# EVMS3_Monitor.net
KiCad netlist of a schematic drawn in EAGLE
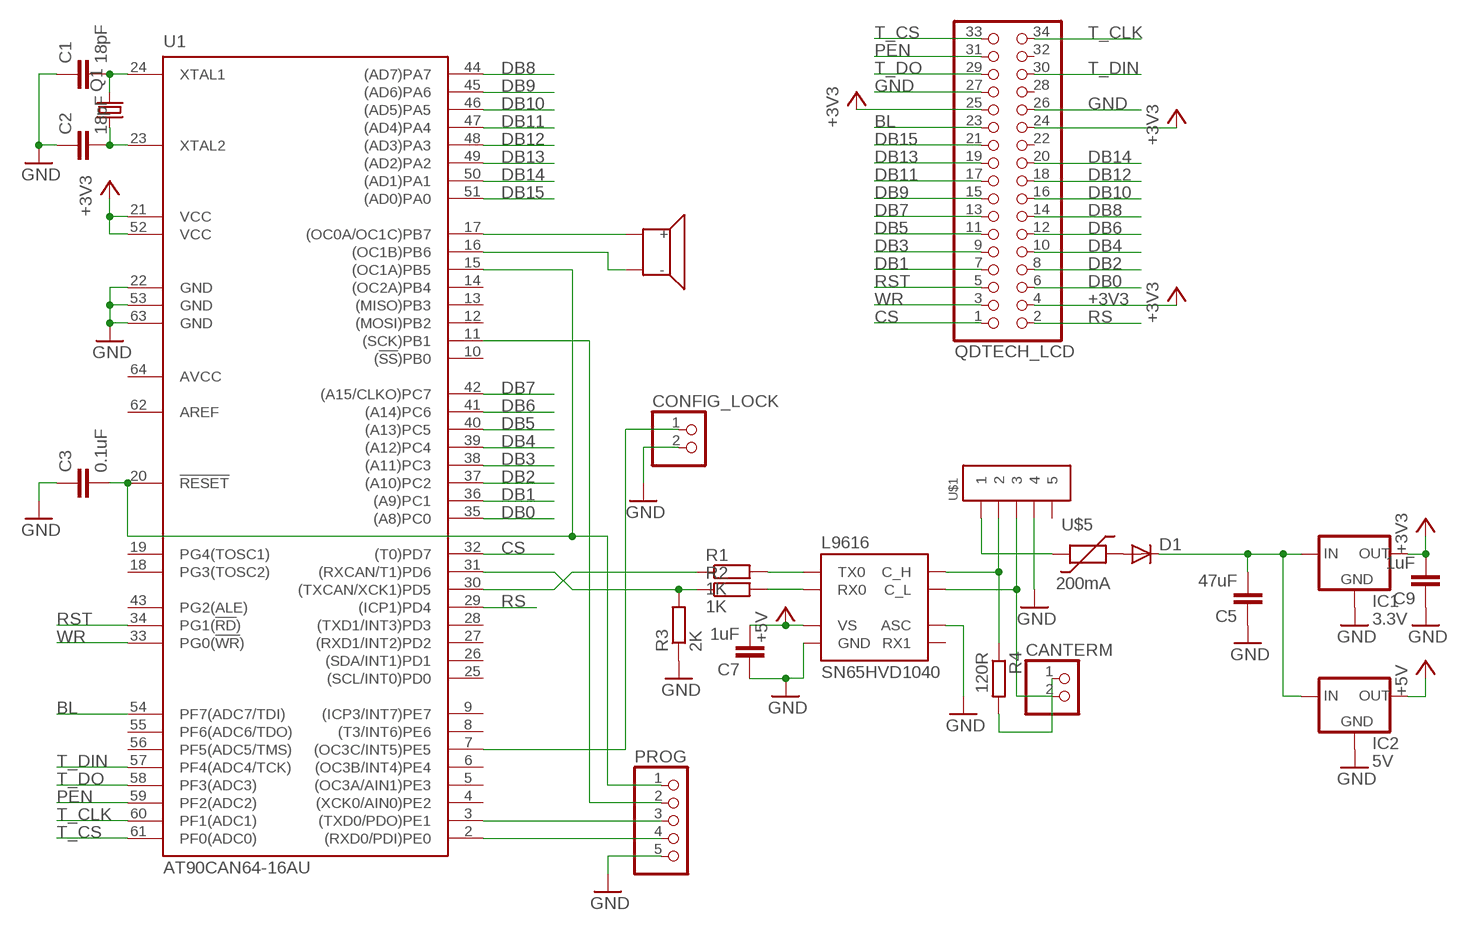
[diagram p0: schematic, sheet 1]

(export (version "E")
  (design (tool "Eeschema 10.0.6"))
  (components
    (comp (ref "C1")
      (value "18pF")
      (footprint "eagle-import:C0805")
      (libsource (lib "eagle-import") (part "C-EUC0805"))
    )
    (comp (ref "C2")
      (value "18pF")
      (footprint "eagle-import:C0805")
      (libsource (lib "eagle-import") (part "C-EUC0805"))
    )
    (comp (ref "C3")
      (value "0.1uF")
      (footprint "eagle-import:C1206")
      (libsource (lib "eagle-import") (part "C-EUC1206"))
    )
    (comp (ref "C5")
      (value "47uF")
      (footprint "eagle-import:C1206")
      (libsource (lib "eagle-import") (part "C-EUC1206"))
    )
    (comp (ref "C7")
      (value "1uF")
      (footprint "eagle-import:C1206")
      (libsource (lib "eagle-import") (part "C-EUC1206"))
    )
    (comp (ref "C9")
      (value "1uF")
      (footprint "eagle-import:C1206")
      (libsource (lib "eagle-import") (part "C-EUC1206"))
    )
    (comp (ref "CANTERM")
      (value "PINHD-1X2")
      (footprint "eagle-import:1X02")
      (libsource (lib "eagle-import") (part "PINHD-1X2"))
    )
    (comp (ref "CONFIG_LOCK")
      (value "PINHD-1X2")
      (footprint "eagle-import:1X02")
      (libsource (lib "eagle-import") (part "PINHD-1X2"))
    )
    (comp (ref "D1")
      (value "DIODE-SOD123")
      (footprint "eagle-import:SOD123")
      (libsource (lib "eagle-import") (part "DIODE-SOD123"))
    )
    (comp (ref "IC1")
      (value "3.3V")
      (footprint "eagle-import:SOT89R")
      (libsource (lib "eagle-import") (part "78LXXSOT89"))
    )
    (comp (ref "IC2")
      (value "5V")
      (footprint "eagle-import:SOT89R")
      (libsource (lib "eagle-import") (part "78LXXSOT89"))
    )
    (comp (ref "PROG")
      (value "PINHD-1X5")
      (footprint "eagle-import:1X05")
      (libsource (lib "eagle-import") (part "PINHD-1X5"))
    )
    (comp (ref "Q1")
      (value "CRYSTALCTS406")
      (footprint "eagle-import:CTS406")
      (libsource (lib "eagle-import") (part "CRYSTALCTS406"))
    )
    (comp (ref "QDTECH_LCD")
      (value "PINHD-2X17")
      (footprint "eagle-import:2X17")
      (libsource (lib "eagle-import") (part "PINHD-2X17"))
    )
    (comp (ref "R1")
      (value "1K")
      (footprint "eagle-import:R1206")
      (libsource (lib "eagle-import") (part "R-EU_R1206"))
    )
    (comp (ref "R2")
      (value "1K")
      (footprint "eagle-import:R1206")
      (libsource (lib "eagle-import") (part "R-EU_R1206"))
    )
    (comp (ref "R3")
      (value "2K")
      (footprint "eagle-import:R1206")
      (libsource (lib "eagle-import") (part "R-EU_R1206"))
    )
    (comp (ref "R4")
      (value "120R")
      (footprint "eagle-import:R1206")
      (libsource (lib "eagle-import") (part "R-EU_R1206"))
    )
    (comp (ref "SN65HVD1040")
      (value "L9616")
      (footprint "eagle-import:SOIC8")
      (libsource (lib "eagle-import") (part "L9616"))
    )
    (comp (ref "U$1")
      (value "MOLEX-39502-1005VERT")
      (footprint "eagle-import:MOLEX-39501-1005")
      (libsource (lib "eagle-import") (part "MOLEX-39502-1005VERT"))
    )
    (comp (ref "U$5")
      (value "200mA")
      (footprint "eagle-import:1206")
      (libsource (lib "eagle-import") (part "1206_POLYSWITCH"))
    )
    (comp (ref "U$6")
      (value "MURATA_PIEZO")
      (footprint "eagle-import:PKLCS1212E_PIEZO")
      (libsource (lib "eagle-import") (part "MURATA_PIEZO"))
    )
    (comp (ref "U1")
      (value "AT90CAN64-16AU")
      (footprint "eagle-import:TQFP64-0.8MM")
      (libsource (lib "eagle-import") (part "AT90CAN64-16AU"))
    )
  )
  (nets
    (net (code "1") (name "+3V3") (class "Default")
      (node (ref "C9") (pin "2") (pinfunction "2_2") (pintype "passive"))
      (node (ref "IC1") (pin "2") (pinfunction "OUT_2") (pintype "passive"))
      (node (ref "QDTECH_LCD") (pin "24") (pinfunction "24_24") (pintype "passive"))
      (node (ref "QDTECH_LCD") (pin "25") (pinfunction "25_25") (pintype "passive"))
      (node (ref "QDTECH_LCD") (pin "4") (pinfunction "4_4") (pintype "passive"))
      (node (ref "U1") (pin "21") (pinfunction "VCC_21") (pintype "power_in"))
      (node (ref "U1") (pin "52") (pinfunction "VCC_52") (pintype "power_in"))
    )
    (net (code "2") (name "+5V") (class "Default")
      (node (ref "C7") (pin "2") (pinfunction "2_2") (pintype "passive"))
      (node (ref "IC2") (pin "2") (pinfunction "OUT_2") (pintype "passive"))
      (node (ref "SN65HVD1040") (pin "P$3") (pinfunction "VS_P$3") (pintype "bidirectional"))
    )
    (net (code "3") (name "/AVCC") (class "Default")
      (node (ref "U1") (pin "64") (pinfunction "AVCC_64") (pintype "power_in"))
    )
    (net (code "4") (name "/BL") (class "Default")
      (node (ref "QDTECH_LCD") (pin "23") (pinfunction "23_23") (pintype "passive"))
      (node (ref "U1") (pin "54") (pinfunction "PF7(ADC7/TDI)_54") (pintype "bidirectional"))
    )
    (net (code "5") (name "/CS") (class "Default")
      (node (ref "QDTECH_LCD") (pin "1") (pinfunction "1_1") (pintype "passive"))
      (node (ref "U1") (pin "32") (pinfunction "(T0)PD7_32") (pintype "bidirectional"))
    )
    (net (code "6") (name "/DB0") (class "Default")
      (node (ref "QDTECH_LCD") (pin "6") (pinfunction "6_6") (pintype "passive"))
      (node (ref "U1") (pin "35") (pinfunction "(A8)PC0_35") (pintype "bidirectional"))
    )
    (net (code "7") (name "/DB1") (class "Default")
      (node (ref "QDTECH_LCD") (pin "7") (pinfunction "7_7") (pintype "passive"))
      (node (ref "U1") (pin "36") (pinfunction "(A9)PC1_36") (pintype "bidirectional"))
    )
    (net (code "8") (name "/DB2") (class "Default")
      (node (ref "QDTECH_LCD") (pin "8") (pinfunction "8_8") (pintype "passive"))
      (node (ref "U1") (pin "37") (pinfunction "(A10)PC2_37") (pintype "bidirectional"))
    )
    (net (code "9") (name "/DB3") (class "Default")
      (node (ref "QDTECH_LCD") (pin "9") (pinfunction "9_9") (pintype "passive"))
      (node (ref "U1") (pin "38") (pinfunction "(A11)PC3_38") (pintype "bidirectional"))
    )
    (net (code "10") (name "/DB4") (class "Default")
      (node (ref "QDTECH_LCD") (pin "10") (pinfunction "10_10") (pintype "passive"))
      (node (ref "U1") (pin "39") (pinfunction "(A12)PC4_39") (pintype "bidirectional"))
    )
    (net (code "11") (name "/DB5") (class "Default")
      (node (ref "QDTECH_LCD") (pin "11") (pinfunction "11_11") (pintype "passive"))
      (node (ref "U1") (pin "40") (pinfunction "(A13)PC5_40") (pintype "bidirectional"))
    )
    (net (code "12") (name "/DB6") (class "Default")
      (node (ref "QDTECH_LCD") (pin "12") (pinfunction "12_12") (pintype "passive"))
      (node (ref "U1") (pin "41") (pinfunction "(A14)PC6_41") (pintype "bidirectional"))
    )
    (net (code "13") (name "/DB7") (class "Default")
      (node (ref "QDTECH_LCD") (pin "13") (pinfunction "13_13") (pintype "passive"))
      (node (ref "U1") (pin "42") (pinfunction "(A15/CLKO)PC7_42") (pintype "bidirectional"))
    )
    (net (code "14") (name "/DB8") (class "Default")
      (node (ref "QDTECH_LCD") (pin "14") (pinfunction "14_14") (pintype "passive"))
      (node (ref "U1") (pin "44") (pinfunction "(AD7)PA7_44") (pintype "bidirectional"))
    )
    (net (code "15") (name "/DB9") (class "Default")
      (node (ref "QDTECH_LCD") (pin "15") (pinfunction "15_15") (pintype "passive"))
      (node (ref "U1") (pin "45") (pinfunction "(AD6)PA6_45") (pintype "bidirectional"))
    )
    (net (code "16") (name "/DB10") (class "Default")
      (node (ref "QDTECH_LCD") (pin "16") (pinfunction "16_16") (pintype "passive"))
      (node (ref "U1") (pin "46") (pinfunction "(AD5)PA5_46") (pintype "bidirectional"))
    )
    (net (code "17") (name "/DB11") (class "Default")
      (node (ref "QDTECH_LCD") (pin "17") (pinfunction "17_17") (pintype "passive"))
      (node (ref "U1") (pin "47") (pinfunction "(AD4)PA4_47") (pintype "bidirectional"))
    )
    (net (code "18") (name "/DB12") (class "Default")
      (node (ref "QDTECH_LCD") (pin "18") (pinfunction "18_18") (pintype "passive"))
      (node (ref "U1") (pin "48") (pinfunction "(AD3)PA3_48") (pintype "bidirectional"))
    )
    (net (code "19") (name "/DB13") (class "Default")
      (node (ref "QDTECH_LCD") (pin "19") (pinfunction "19_19") (pintype "passive"))
      (node (ref "U1") (pin "49") (pinfunction "(AD2)PA2_49") (pintype "bidirectional"))
    )
    (net (code "20") (name "/DB14") (class "Default")
      (node (ref "QDTECH_LCD") (pin "20") (pinfunction "20_20") (pintype "passive"))
      (node (ref "U1") (pin "50") (pinfunction "(AD1)PA1_50") (pintype "bidirectional"))
    )
    (net (code "21") (name "/DB15") (class "Default")
      (node (ref "QDTECH_LCD") (pin "21") (pinfunction "21_21") (pintype "passive"))
      (node (ref "U1") (pin "51") (pinfunction "(AD0)PA0_51") (pintype "bidirectional"))
    )
    (net (code "22") (name "/PEN") (class "Default")
      (node (ref "QDTECH_LCD") (pin "31") (pinfunction "31_31") (pintype "passive"))
      (node (ref "U1") (pin "59") (pinfunction "PF2(ADC2)_59") (pintype "bidirectional"))
    )
    (net (code "23") (name "/RS") (class "Default")
      (node (ref "QDTECH_LCD") (pin "2") (pinfunction "2_2") (pintype "passive"))
      (node (ref "U1") (pin "29") (pinfunction "(ICP1)PD4_29") (pintype "bidirectional"))
    )
    (net (code "24") (name "/RST") (class "Default")
      (node (ref "QDTECH_LCD") (pin "5") (pinfunction "5_5") (pintype "passive"))
      (node (ref "U1") (pin "34") (pinfunction "PG1(~{RD})_34") (pintype "bidirectional"))
    )
    (net (code "25") (name "/T_CLK") (class "Default")
      (node (ref "QDTECH_LCD") (pin "34") (pinfunction "34_34") (pintype "passive"))
      (node (ref "U1") (pin "60") (pinfunction "PF1(ADC1)_60") (pintype "bidirectional"))
    )
    (net (code "26") (name "/T_CS") (class "Default")
      (node (ref "QDTECH_LCD") (pin "33") (pinfunction "33_33") (pintype "passive"))
      (node (ref "U1") (pin "61") (pinfunction "PF0(ADC0)_61") (pintype "bidirectional"))
    )
    (net (code "27") (name "/T_DIN") (class "Default")
      (node (ref "QDTECH_LCD") (pin "30") (pinfunction "30_30") (pintype "passive"))
      (node (ref "U1") (pin "57") (pinfunction "PF4(ADC4/TCK)_57") (pintype "bidirectional"))
    )
    (net (code "28") (name "/T_DO") (class "Default")
      (node (ref "QDTECH_LCD") (pin "29") (pinfunction "29_29") (pintype "passive"))
      (node (ref "U1") (pin "58") (pinfunction "PF3(ADC3)_58") (pintype "bidirectional"))
    )
    (net (code "29") (name "/WR") (class "Default")
      (node (ref "QDTECH_LCD") (pin "3") (pinfunction "3_3") (pintype "passive"))
      (node (ref "U1") (pin "33") (pinfunction "PG0(~{WR})_33") (pintype "bidirectional"))
    )
    (net (code "30") (name "GND") (class "Default")
      (node (ref "C1") (pin "1") (pinfunction "1_1") (pintype "passive"))
      (node (ref "C2") (pin "1") (pinfunction "1_1") (pintype "passive"))
      (node (ref "C3") (pin "1") (pinfunction "1_1") (pintype "passive"))
      (node (ref "C5") (pin "1") (pinfunction "1_1") (pintype "passive"))
      (node (ref "C7") (pin "1") (pinfunction "1_1") (pintype "passive"))
      (node (ref "C9") (pin "1") (pinfunction "1_1") (pintype "passive"))
      (node (ref "CONFIG_LOCK") (pin "2") (pinfunction "2_2") (pintype "passive"))
      (node (ref "IC1") (pin "4") (pinfunction "GND_4") (pintype "input"))
      (node (ref "IC2") (pin "4") (pinfunction "GND_4") (pintype "input"))
      (node (ref "PROG") (pin "5") (pinfunction "5_5") (pintype "passive"))
      (node (ref "QDTECH_LCD") (pin "26") (pinfunction "26_26") (pintype "passive"))
      (node (ref "QDTECH_LCD") (pin "27") (pinfunction "27_27") (pintype "passive"))
      (node (ref "R3") (pin "1") (pinfunction "1_1") (pintype "passive"))
      (node (ref "SN65HVD1040") (pin "P$2") (pinfunction "GND_P$2") (pintype "bidirectional"))
      (node (ref "SN65HVD1040") (pin "P$8") (pinfunction "ASC_P$8") (pintype "bidirectional"))
      (node (ref "U$1") (pin "4") (pinfunction "4_4") (pintype "bidirectional"))
      (node (ref "U1") (pin "22") (pinfunction "GND_22") (pintype "power_in"))
      (node (ref "U1") (pin "53") (pinfunction "GND_53") (pintype "power_in"))
      (node (ref "U1") (pin "63") (pinfunction "GND_63") (pintype "power_in"))
    )
    (net (code "31") (name "Net-(CANTERM-Pad1)") (class "Default")
      (node (ref "CANTERM") (pin "1") (pinfunction "1_1") (pintype "passive"))
      (node (ref "R4") (pin "2") (pinfunction "2_2") (pintype "passive"))
    )
    (net (code "32") (name "Net-(D1-PadA)") (class "Default")
      (node (ref "D1") (pin "A") (pinfunction "A_A") (pintype "passive"))
      (node (ref "U$5") (pin "P$2") (pinfunction "P$2_P$2") (pintype "bidirectional"))
    )
    (net (code "33") (name "Net-(IC1-IN)") (class "Default")
      (node (ref "C5") (pin "2") (pinfunction "2_2") (pintype "passive"))
      (node (ref "D1") (pin "C") (pinfunction "C_C") (pintype "passive"))
      (node (ref "IC1") (pin "1") (pinfunction "IN_1") (pintype "input"))
      (node (ref "IC2") (pin "1") (pinfunction "IN_1") (pintype "input"))
    )
    (net (code "34") (name "Net-(Q1-2)") (class "Default")
      (node (ref "C1") (pin "2") (pinfunction "2_2") (pintype "passive"))
      (node (ref "Q1") (pin "3") (pinfunction "2_3") (pintype "passive"))
      (node (ref "U1") (pin "24") (pinfunction "XTAL1_24") (pintype "passive"))
    )
    (net (code "35") (name "Net-(SN65HVD1040-C_H)") (class "Default")
      (node (ref "R4") (pin "1") (pinfunction "1_1") (pintype "passive"))
      (node (ref "SN65HVD1040") (pin "P$7") (pinfunction "C_H_P$7") (pintype "bidirectional"))
      (node (ref "U$1") (pin "2") (pinfunction "2_2") (pintype "bidirectional"))
    )
    (net (code "36") (name "Net-(SN65HVD1040-C_L)") (class "Default")
      (node (ref "CANTERM") (pin "2") (pinfunction "2_2") (pintype "passive"))
      (node (ref "SN65HVD1040") (pin "P$6") (pinfunction "C_L_P$6") (pintype "bidirectional"))
      (node (ref "U$1") (pin "3") (pinfunction "3_3") (pintype "bidirectional"))
    )
    (net (code "37") (name "Net-(SN65HVD1040-RX0)") (class "Default")
      (node (ref "R2") (pin "2") (pinfunction "2_2") (pintype "passive"))
      (node (ref "SN65HVD1040") (pin "P$4") (pinfunction "RX0_P$4") (pintype "bidirectional"))
    )
    (net (code "38") (name "Net-(SN65HVD1040-TX0)") (class "Default")
      (node (ref "R1") (pin "2") (pinfunction "2_2") (pintype "passive"))
      (node (ref "SN65HVD1040") (pin "P$1") (pinfunction "TX0_P$1") (pintype "bidirectional"))
    )
    (net (code "39") (name "Net-(U$1-Pad1)") (class "Default")
      (node (ref "U$1") (pin "1") (pinfunction "1_1") (pintype "bidirectional"))
      (node (ref "U$5") (pin "P$1") (pinfunction "P$1_P$1") (pintype "bidirectional"))
    )
    (net (code "40") (name "Net-(U$6-+)") (class "Default")
      (node (ref "U$6") (pin "1") (pinfunction "+_1") (pintype "bidirectional"))
      (node (ref "U1") (pin "17") (pinfunction "(OC0A/OC1C)PB7_17") (pintype "bidirectional"))
    )
    (net (code "41") (name "Net-(U$6--)") (class "Default")
      (node (ref "U$6") (pin "2") (pinfunction "-_2") (pintype "bidirectional"))
      (node (ref "U1") (pin "16") (pinfunction "(OC1B)PB6_16") (pintype "bidirectional"))
    )
    (net (code "42") (name "Net-(U1-(OC1A)PB5)") (class "Default")
      (node (ref "C3") (pin "2") (pinfunction "2_2") (pintype "passive"))
      (node (ref "PROG") (pin "1") (pinfunction "1_1") (pintype "passive"))
      (node (ref "U1") (pin "15") (pinfunction "(OC1A)PB5_15") (pintype "bidirectional"))
      (node (ref "U1") (pin "20") (pinfunction "~{RESET}_20") (pintype "input"))
    )
    (net (code "43") (name "Net-(U1-(OC3C{slash}INT5)PE5)") (class "Default")
      (node (ref "CONFIG_LOCK") (pin "1") (pinfunction "1_1") (pintype "passive"))
      (node (ref "U1") (pin "7") (pinfunction "(OC3C/INT5)PE5_7") (pintype "bidirectional"))
    )
    (net (code "44") (name "Net-(U1-(RXCAN{slash}T1)PD6)") (class "Default")
      (node (ref "R2") (pin "1") (pinfunction "1_1") (pintype "passive"))
      (node (ref "R3") (pin "2") (pinfunction "2_2") (pintype "passive"))
      (node (ref "U1") (pin "31") (pinfunction "(RXCAN/T1)PD6_31") (pintype "bidirectional"))
    )
    (net (code "45") (name "Net-(U1-(RXD0{slash}PDI)PE0)") (class "Default")
      (node (ref "PROG") (pin "4") (pinfunction "4_4") (pintype "passive"))
      (node (ref "U1") (pin "2") (pinfunction "(RXD0/PDI)PE0_2") (pintype "bidirectional"))
    )
    (net (code "46") (name "Net-(U1-(SCK)PB1)") (class "Default")
      (node (ref "PROG") (pin "2") (pinfunction "2_2") (pintype "passive"))
      (node (ref "U1") (pin "11") (pinfunction "(SCK)PB1_11") (pintype "bidirectional"))
    )
    (net (code "47") (name "Net-(U1-(TXCAN{slash}XCK1)PD5)") (class "Default")
      (node (ref "R1") (pin "1") (pinfunction "1_1") (pintype "passive"))
      (node (ref "U1") (pin "30") (pinfunction "(TXCAN/XCK1)PD5_30") (pintype "bidirectional"))
    )
    (net (code "48") (name "Net-(U1-(TXD0{slash}PDO)PE1)") (class "Default")
      (node (ref "PROG") (pin "3") (pinfunction "3_3") (pintype "passive"))
      (node (ref "U1") (pin "3") (pinfunction "(TXD0/PDO)PE1_3") (pintype "bidirectional"))
    )
    (net (code "49") (name "Net-(U1-XTAL2)") (class "Default")
      (node (ref "C2") (pin "2") (pinfunction "2_2") (pintype "passive"))
      (node (ref "Q1") (pin "1") (pinfunction "1_1") (pintype "passive"))
      (node (ref "U1") (pin "23") (pinfunction "XTAL2_23") (pintype "passive"))
    )
    (net (code "50") (name "unconnected-(QDTECH_LCD-Pad22)") (class "Default")
      (node (ref "QDTECH_LCD") (pin "22") (pinfunction "22_22") (pintype "passive"))
    )
    (net (code "51") (name "unconnected-(QDTECH_LCD-Pad28)") (class "Default")
      (node (ref "QDTECH_LCD") (pin "28") (pinfunction "28_28") (pintype "passive"))
    )
    (net (code "52") (name "unconnected-(QDTECH_LCD-Pad32)") (class "Default")
      (node (ref "QDTECH_LCD") (pin "32") (pinfunction "32_32") (pintype "passive"))
    )
    (net (code "53") (name "unconnected-(SN65HVD1040-RX1-PadP$5)") (class "Default")
      (node (ref "SN65HVD1040") (pin "P$5") (pinfunction "RX1_P$5") (pintype "bidirectional"))
    )
    (net (code "54") (name "unconnected-(U$1-Pad5)") (class "Default")
      (node (ref "U$1") (pin "5") (pinfunction "5_5") (pintype "bidirectional"))
    )
    (net (code "55") (name "unconnected-(U1-(ICP3{slash}INT7)PE7-Pad9)") (class "Default")
      (node (ref "U1") (pin "9") (pinfunction "(ICP3/INT7)PE7_9") (pintype "bidirectional"))
    )
    (net (code "56") (name "unconnected-(U1-(MISO)PB3-Pad13)") (class "Default")
      (node (ref "U1") (pin "13") (pinfunction "(MISO)PB3_13") (pintype "bidirectional"))
    )
    (net (code "57") (name "unconnected-(U1-(MOSI)PB2-Pad12)") (class "Default")
      (node (ref "U1") (pin "12") (pinfunction "(MOSI)PB2_12") (pintype "bidirectional"))
    )
    (net (code "58") (name "unconnected-(U1-(OC2A)PB4-Pad14)") (class "Default")
      (node (ref "U1") (pin "14") (pinfunction "(OC2A)PB4_14") (pintype "bidirectional"))
    )
    (net (code "59") (name "unconnected-(U1-(OC3A{slash}AIN1)PE3-Pad5)") (class "Default")
      (node (ref "U1") (pin "5") (pinfunction "(OC3A/AIN1)PE3_5") (pintype "bidirectional"))
    )
    (net (code "60") (name "unconnected-(U1-(OC3B{slash}INT4)PE4-Pad6)") (class "Default")
      (node (ref "U1") (pin "6") (pinfunction "(OC3B/INT4)PE4_6") (pintype "bidirectional"))
    )
    (net (code "61") (name "unconnected-(U1-(RXD1{slash}INT2)PD2-Pad27)") (class "Default")
      (node (ref "U1") (pin "27") (pinfunction "(RXD1/INT2)PD2_27") (pintype "bidirectional"))
    )
    (net (code "62") (name "unconnected-(U1-(SCL{slash}INT0)PD0-Pad25)") (class "Default")
      (node (ref "U1") (pin "25") (pinfunction "(SCL/INT0)PD0_25") (pintype "bidirectional"))
    )
    (net (code "63") (name "unconnected-(U1-(SDA{slash}INT1)PD1-Pad26)") (class "Default")
      (node (ref "U1") (pin "26") (pinfunction "(SDA/INT1)PD1_26") (pintype "bidirectional"))
    )
    (net (code "64") (name "unconnected-(U1-(T3{slash}INT6)PE6-Pad8)") (class "Default")
      (node (ref "U1") (pin "8") (pinfunction "(T3/INT6)PE6_8") (pintype "bidirectional"))
    )
    (net (code "65") (name "unconnected-(U1-(TXD1{slash}INT3)PD3-Pad28)") (class "Default")
      (node (ref "U1") (pin "28") (pinfunction "(TXD1/INT3)PD3_28") (pintype "bidirectional"))
    )
    (net (code "66") (name "unconnected-(U1-(XCK0{slash}AIN0)PE2-Pad4)") (class "Default")
      (node (ref "U1") (pin "4") (pinfunction "(XCK0/AIN0)PE2_4") (pintype "bidirectional"))
    )
    (net (code "67") (name "unconnected-(U1-(~{SS})PB0-Pad10)") (class "Default")
      (node (ref "U1") (pin "10") (pinfunction "(~{SS})PB0_10") (pintype "bidirectional"))
    )
    (net (code "68") (name "unconnected-(U1-AREF-Pad62)") (class "Default")
      (node (ref "U1") (pin "62") (pinfunction "AREF_62") (pintype "passive"))
    )
    (net (code "69") (name "unconnected-(U1-PF5(ADC5{slash}TMS)-Pad56)") (class "Default")
      (node (ref "U1") (pin "56") (pinfunction "PF5(ADC5/TMS)_56") (pintype "bidirectional"))
    )
    (net (code "70") (name "unconnected-(U1-PF6(ADC6{slash}TDO)-Pad55)") (class "Default")
      (node (ref "U1") (pin "55") (pinfunction "PF6(ADC6/TDO)_55") (pintype "bidirectional"))
    )
    (net (code "71") (name "unconnected-(U1-PG2(ALE)-Pad43)") (class "Default")
      (node (ref "U1") (pin "43") (pinfunction "PG2(ALE)_43") (pintype "bidirectional"))
    )
    (net (code "72") (name "unconnected-(U1-PG3(TOSC2)-Pad18)") (class "Default")
      (node (ref "U1") (pin "18") (pinfunction "PG3(TOSC2)_18") (pintype "bidirectional"))
    )
    (net (code "73") (name "unconnected-(U1-PG4(TOSC1)-Pad19)") (class "Default")
      (node (ref "U1") (pin "19") (pinfunction "PG4(TOSC1)_19") (pintype "bidirectional"))
    )
  )
)
